# enhanced-dual-joystick.net
KiCad netlist of a schematic drawn in EAGLE
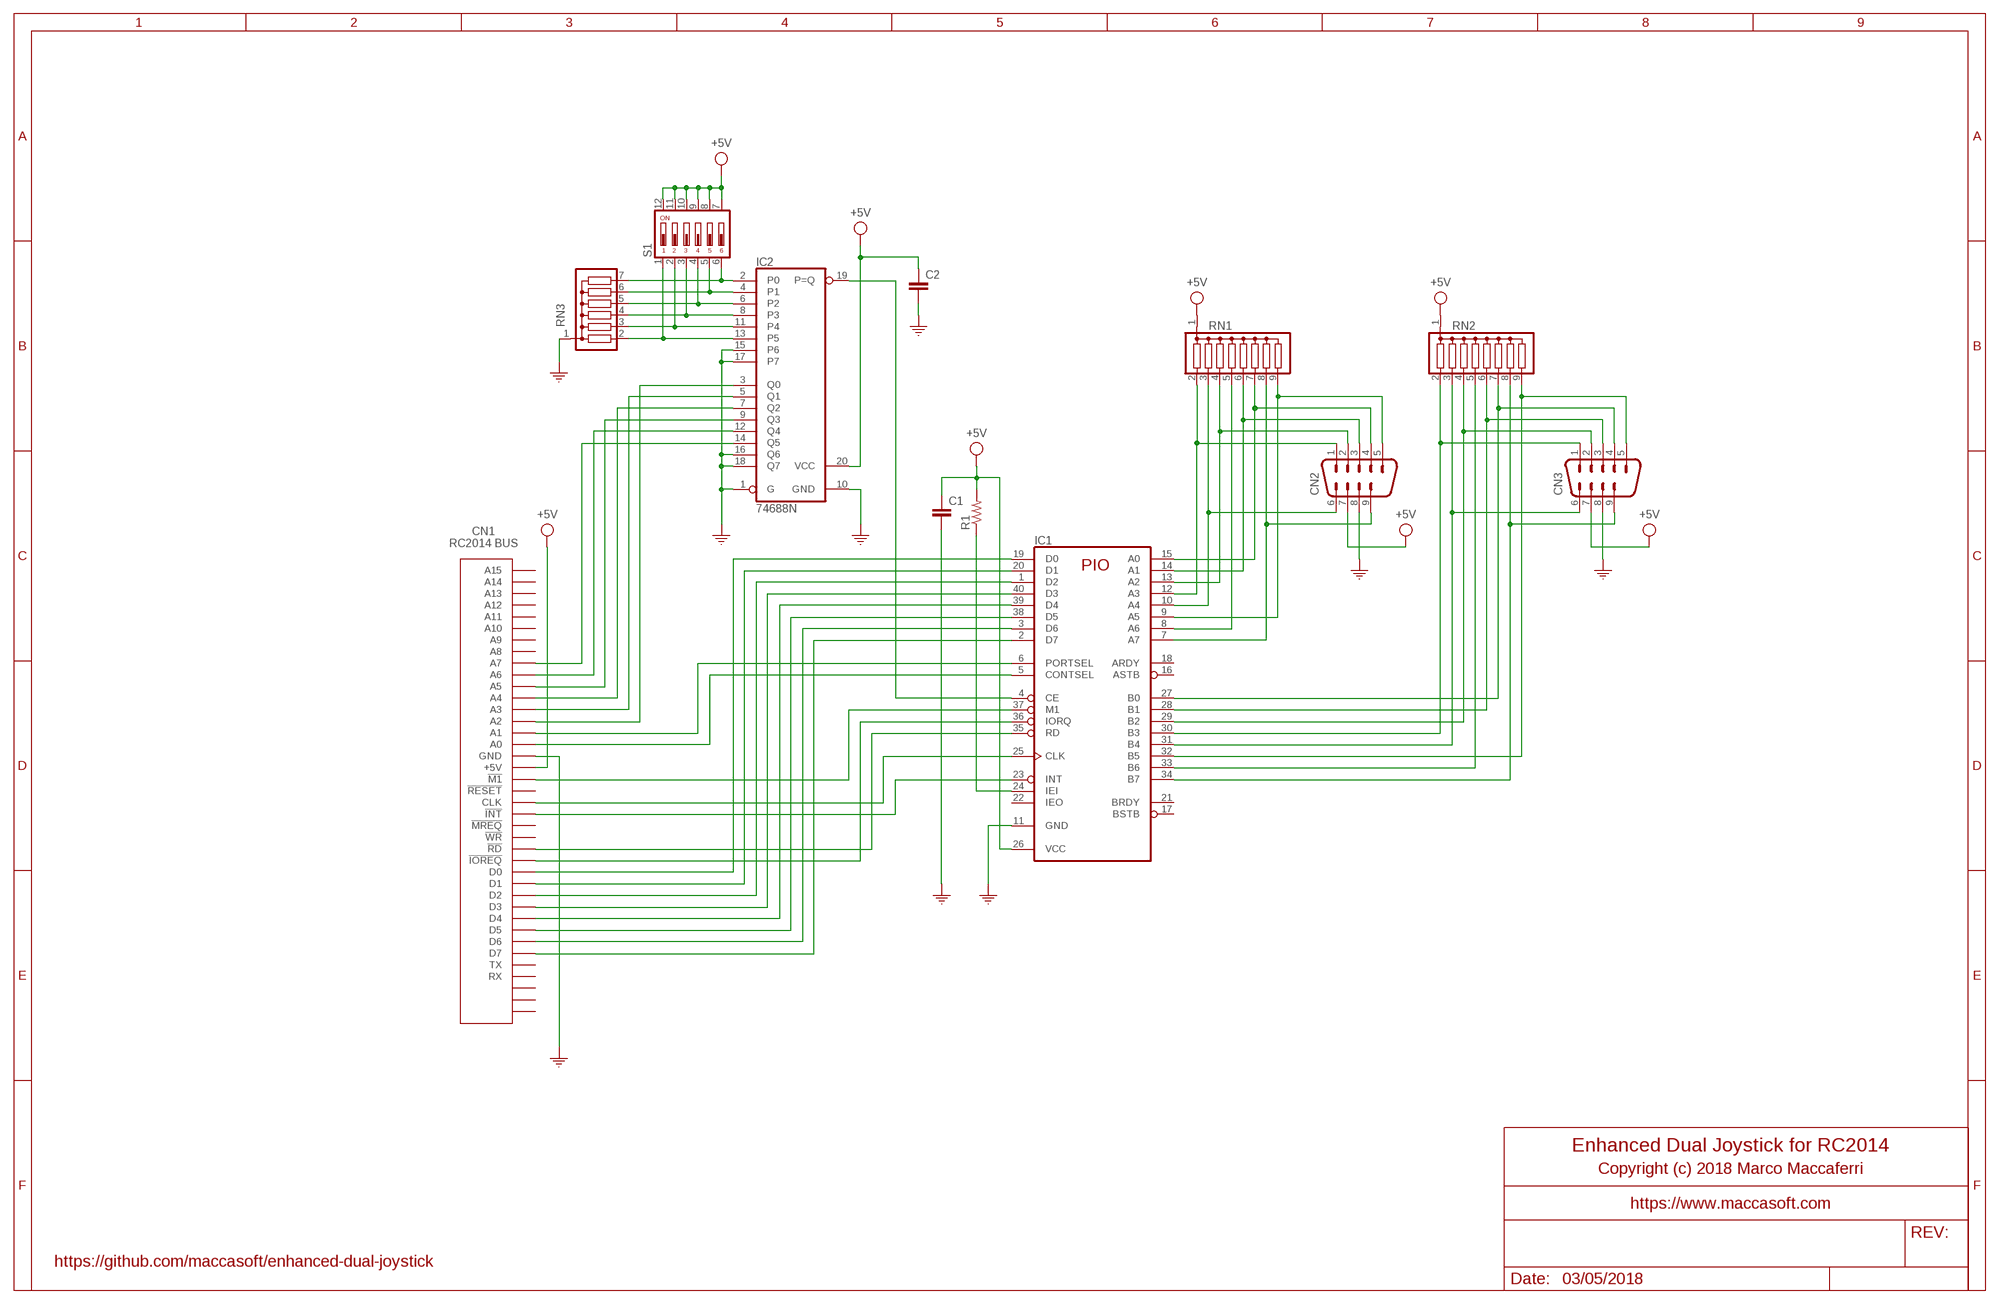
[diagram p0: schematic, sheet 1]

(export (version "E")
  (design (tool "Eeschema 10.0.6"))
  (components
    (comp (ref "C1")
      (value "C-EU050-025X075")
      (footprint "eagle-import:C050-025X075")
      (libsource (lib "eagle-import") (part "C-EU050-025X075"))
    )
    (comp (ref "C2")
      (value "C-EU050-025X075")
      (footprint "eagle-import:C050-025X075")
      (libsource (lib "eagle-import") (part "C-EU050-025X075"))
    )
    (comp (ref "CN1")
      (value "RC2014BUS")
      (footprint "eagle-import:RC2014BUS")
      (fields (field (name "MPN") "PRPC040SBAN-M71RC"))
      (libsource (lib "eagle-import") (part "RC2014BUS"))
    )
    (comp (ref "CN2")
      (value "M09H")
      (footprint "eagle-import:M09H")
      (libsource (lib "eagle-import") (part "M09H"))
    )
    (comp (ref "CN3")
      (value "M09H")
      (footprint "eagle-import:M09H")
      (libsource (lib "eagle-import") (part "M09H"))
    )
    (comp (ref "IC1")
      (value "Z80PIO")
      (footprint "eagle-import:DIL40")
      (libsource (lib "eagle-import") (part "Z80PIO"))
    )
    (comp (ref "IC2")
      (value "74688N")
      (footprint "eagle-import:DIL20")
      (libsource (lib "eagle-import") (part "74688N"))
    )
    (comp (ref "R1")
      (value "R-US_0207/10")
      (footprint "eagle-import:0207_10")
      (libsource (lib "eagle-import") (part "R-US_0207/10"))
    )
    (comp (ref "RN1")
      (value "G08R")
      (footprint "eagle-import:SIL9")
      (libsource (lib "eagle-import") (part "G08R"))
    )
    (comp (ref "RN2")
      (value "G08R")
      (footprint "eagle-import:SIL9")
      (libsource (lib "eagle-import") (part "G08R"))
    )
    (comp (ref "RN3")
      (value "G06R")
      (footprint "eagle-import:SIL7")
      (libsource (lib "eagle-import") (part "G06R"))
    )
    (comp (ref "S1")
      (value "DIP06YL")
      (footprint "eagle-import:DIP06YL")
      (libsource (lib "eagle-import") (part "DIP06YL"))
    )
  )
  (nets
    (net (code "1") (name "+5V") (class "Default")
      (node (ref "C1") (pin "1") (pinfunction "1_1") (pintype "passive"))
      (node (ref "C2") (pin "1") (pinfunction "1_1") (pintype "passive"))
      (node (ref "CN1") (pin "+5V") (pinfunction "+5V_+5V") (pintype "bidirectional"))
      (node (ref "CN2") (pin "7") (pinfunction "7_7") (pintype "passive"))
      (node (ref "CN3") (pin "7") (pinfunction "7_7") (pintype "passive"))
      (node (ref "IC1") (pin "26") (pinfunction "VCC_26") (pintype "power_in"))
      (node (ref "IC2") (pin "20") (pinfunction "VCC_20") (pintype "power_in"))
      (node (ref "R1") (pin "2") (pinfunction "2_2") (pintype "passive"))
      (node (ref "RN1") (pin "1") (pinfunction "1_1") (pintype "passive"))
      (node (ref "RN2") (pin "1") (pinfunction "1_1") (pintype "passive"))
      (node (ref "S1") (pin "10") (pinfunction "10_10") (pintype "passive"))
      (node (ref "S1") (pin "11") (pinfunction "11_11") (pintype "passive"))
      (node (ref "S1") (pin "12") (pinfunction "12_12") (pintype "passive"))
      (node (ref "S1") (pin "7") (pinfunction "7_7") (pintype "passive"))
      (node (ref "S1") (pin "8") (pinfunction "8_8") (pintype "passive"))
      (node (ref "S1") (pin "9") (pinfunction "9_9") (pintype "passive"))
    )
    (net (code "2") (name "GND") (class "Default")
      (node (ref "C1") (pin "2") (pinfunction "2_2") (pintype "passive"))
      (node (ref "C2") (pin "2") (pinfunction "2_2") (pintype "passive"))
      (node (ref "CN1") (pin "GND") (pinfunction "GND_GND") (pintype "bidirectional"))
      (node (ref "CN2") (pin "8") (pinfunction "8_8") (pintype "passive"))
      (node (ref "CN3") (pin "8") (pinfunction "8_8") (pintype "passive"))
      (node (ref "IC1") (pin "11") (pinfunction "GND_11") (pintype "power_in"))
      (node (ref "IC2") (pin "1") (pinfunction "G_1") (pintype "input"))
      (node (ref "IC2") (pin "10") (pinfunction "GND_10") (pintype "power_in"))
      (node (ref "IC2") (pin "15") (pinfunction "P6_15") (pintype "input"))
      (node (ref "IC2") (pin "16") (pinfunction "Q6_16") (pintype "input"))
      (node (ref "IC2") (pin "17") (pinfunction "P7_17") (pintype "input"))
      (node (ref "IC2") (pin "18") (pinfunction "Q7_18") (pintype "input"))
      (node (ref "RN3") (pin "1") (pinfunction "1_1") (pintype "passive"))
    )
    (net (code "3") (name "Net-(CN1-~{INT})") (class "Default")
      (node (ref "CN1") (pin "!INT!") (pinfunction "~{INT}_!INT!") (pintype "bidirectional"))
      (node (ref "IC1") (pin "23") (pinfunction "INT_23") (pintype "output"))
    )
    (net (code "4") (name "Net-(CN1-~{IOREQ})") (class "Default")
      (node (ref "CN1") (pin "!IOREQ!") (pinfunction "~{IOREQ}_!IOREQ!") (pintype "bidirectional"))
      (node (ref "IC1") (pin "36") (pinfunction "IORQ_36") (pintype "input"))
    )
    (net (code "5") (name "Net-(CN1-~{M1})") (class "Default")
      (node (ref "CN1") (pin "!M1!") (pinfunction "~{M1}_!M1!") (pintype "bidirectional"))
      (node (ref "IC1") (pin "37") (pinfunction "M1_37") (pintype "input"))
    )
    (net (code "6") (name "Net-(CN1-~{RD})") (class "Default")
      (node (ref "CN1") (pin "!RD!") (pinfunction "~{RD}_!RD!") (pintype "bidirectional"))
      (node (ref "IC1") (pin "35") (pinfunction "RD_35") (pintype "input"))
    )
    (net (code "7") (name "Net-(IC1-A0)") (class "Default")
      (node (ref "CN2") (pin "4") (pinfunction "4_4") (pintype "passive"))
      (node (ref "IC1") (pin "15") (pinfunction "A0_15") (pintype "bidirectional"))
      (node (ref "RN1") (pin "7") (pinfunction "7_7") (pintype "passive"))
    )
    (net (code "8") (name "Net-(IC1-A1)") (class "Default")
      (node (ref "CN2") (pin "3") (pinfunction "3_3") (pintype "passive"))
      (node (ref "IC1") (pin "14") (pinfunction "A1_14") (pintype "bidirectional"))
      (node (ref "RN1") (pin "6") (pinfunction "6_6") (pintype "passive"))
    )
    (net (code "9") (name "Net-(IC1-A2)") (class "Default")
      (node (ref "CN2") (pin "2") (pinfunction "2_2") (pintype "passive"))
      (node (ref "IC1") (pin "13") (pinfunction "A2_13") (pintype "bidirectional"))
      (node (ref "RN1") (pin "4") (pinfunction "4_4") (pintype "passive"))
    )
    (net (code "10") (name "Net-(IC1-A3)") (class "Default")
      (node (ref "CN2") (pin "1") (pinfunction "1_1") (pintype "passive"))
      (node (ref "IC1") (pin "12") (pinfunction "A3_12") (pintype "bidirectional"))
      (node (ref "RN1") (pin "2") (pinfunction "2_2") (pintype "passive"))
    )
    (net (code "11") (name "Net-(IC1-A4)") (class "Default")
      (node (ref "CN2") (pin "6") (pinfunction "6_6") (pintype "passive"))
      (node (ref "IC1") (pin "10") (pinfunction "A4_10") (pintype "bidirectional"))
      (node (ref "RN1") (pin "3") (pinfunction "3_3") (pintype "passive"))
    )
    (net (code "12") (name "Net-(IC1-A5)") (class "Default")
      (node (ref "CN2") (pin "5") (pinfunction "5_5") (pintype "passive"))
      (node (ref "IC1") (pin "9") (pinfunction "A5_9") (pintype "bidirectional"))
      (node (ref "RN1") (pin "9") (pinfunction "9_9") (pintype "passive"))
    )
    (net (code "13") (name "Net-(IC1-A6)") (class "Default")
      (node (ref "IC1") (pin "8") (pinfunction "A6_8") (pintype "bidirectional"))
      (node (ref "RN1") (pin "5") (pinfunction "5_5") (pintype "passive"))
    )
    (net (code "14") (name "Net-(IC1-A7)") (class "Default")
      (node (ref "CN2") (pin "9") (pinfunction "9_9") (pintype "passive"))
      (node (ref "IC1") (pin "7") (pinfunction "A7_7") (pintype "bidirectional"))
      (node (ref "RN1") (pin "8") (pinfunction "8_8") (pintype "passive"))
    )
    (net (code "15") (name "Net-(IC1-B0)") (class "Default")
      (node (ref "CN3") (pin "4") (pinfunction "4_4") (pintype "passive"))
      (node (ref "IC1") (pin "27") (pinfunction "B0_27") (pintype "bidirectional"))
      (node (ref "RN2") (pin "7") (pinfunction "7_7") (pintype "passive"))
    )
    (net (code "16") (name "Net-(IC1-B1)") (class "Default")
      (node (ref "CN3") (pin "3") (pinfunction "3_3") (pintype "passive"))
      (node (ref "IC1") (pin "28") (pinfunction "B1_28") (pintype "bidirectional"))
      (node (ref "RN2") (pin "6") (pinfunction "6_6") (pintype "passive"))
    )
    (net (code "17") (name "Net-(IC1-B2)") (class "Default")
      (node (ref "CN3") (pin "2") (pinfunction "2_2") (pintype "passive"))
      (node (ref "IC1") (pin "29") (pinfunction "B2_29") (pintype "bidirectional"))
      (node (ref "RN2") (pin "4") (pinfunction "4_4") (pintype "passive"))
    )
    (net (code "18") (name "Net-(IC1-B3)") (class "Default")
      (node (ref "CN3") (pin "1") (pinfunction "1_1") (pintype "passive"))
      (node (ref "IC1") (pin "30") (pinfunction "B3_30") (pintype "bidirectional"))
      (node (ref "RN2") (pin "2") (pinfunction "2_2") (pintype "passive"))
    )
    (net (code "19") (name "Net-(IC1-B4)") (class "Default")
      (node (ref "CN3") (pin "6") (pinfunction "6_6") (pintype "passive"))
      (node (ref "IC1") (pin "31") (pinfunction "B4_31") (pintype "bidirectional"))
      (node (ref "RN2") (pin "3") (pinfunction "3_3") (pintype "passive"))
    )
    (net (code "20") (name "Net-(IC1-B5)") (class "Default")
      (node (ref "CN3") (pin "5") (pinfunction "5_5") (pintype "passive"))
      (node (ref "IC1") (pin "32") (pinfunction "B5_32") (pintype "bidirectional"))
      (node (ref "RN2") (pin "9") (pinfunction "9_9") (pintype "passive"))
    )
    (net (code "21") (name "Net-(IC1-B6)") (class "Default")
      (node (ref "IC1") (pin "33") (pinfunction "B6_33") (pintype "bidirectional"))
      (node (ref "RN2") (pin "5") (pinfunction "5_5") (pintype "passive"))
    )
    (net (code "22") (name "Net-(IC1-B7)") (class "Default")
      (node (ref "CN3") (pin "9") (pinfunction "9_9") (pintype "passive"))
      (node (ref "IC1") (pin "34") (pinfunction "B7_34") (pintype "bidirectional"))
      (node (ref "RN2") (pin "8") (pinfunction "8_8") (pintype "passive"))
    )
    (net (code "23") (name "Net-(IC1-CE)") (class "Default")
      (node (ref "IC1") (pin "4") (pinfunction "CE_4") (pintype "input"))
      (node (ref "IC2") (pin "19") (pinfunction "P=Q_19") (pintype "output"))
    )
    (net (code "24") (name "Net-(IC1-CLK)") (class "Default")
      (node (ref "CN1") (pin "CLK") (pinfunction "CLK_CLK") (pintype "bidirectional"))
      (node (ref "IC1") (pin "25") (pinfunction "CLK_25") (pintype "input"))
    )
    (net (code "25") (name "Net-(IC1-CONTSEL)") (class "Default")
      (node (ref "CN1") (pin "A0") (pinfunction "A0_A0") (pintype "bidirectional"))
      (node (ref "IC1") (pin "5") (pinfunction "CONTSEL_5") (pintype "input"))
    )
    (net (code "26") (name "Net-(IC1-D0)") (class "Default")
      (node (ref "CN1") (pin "D0") (pinfunction "D0_D0") (pintype "bidirectional"))
      (node (ref "IC1") (pin "19") (pinfunction "D0_19") (pintype "bidirectional"))
    )
    (net (code "27") (name "Net-(IC1-D1)") (class "Default")
      (node (ref "CN1") (pin "D1") (pinfunction "D1_D1") (pintype "bidirectional"))
      (node (ref "IC1") (pin "20") (pinfunction "D1_20") (pintype "bidirectional"))
    )
    (net (code "28") (name "Net-(IC1-D2)") (class "Default")
      (node (ref "CN1") (pin "D2") (pinfunction "D2_D2") (pintype "bidirectional"))
      (node (ref "IC1") (pin "1") (pinfunction "D2_1") (pintype "bidirectional"))
    )
    (net (code "29") (name "Net-(IC1-D3)") (class "Default")
      (node (ref "CN1") (pin "D3") (pinfunction "D3_D3") (pintype "bidirectional"))
      (node (ref "IC1") (pin "40") (pinfunction "D3_40") (pintype "bidirectional"))
    )
    (net (code "30") (name "Net-(IC1-D4)") (class "Default")
      (node (ref "CN1") (pin "D4") (pinfunction "D4_D4") (pintype "bidirectional"))
      (node (ref "IC1") (pin "39") (pinfunction "D4_39") (pintype "bidirectional"))
    )
    (net (code "31") (name "Net-(IC1-D5)") (class "Default")
      (node (ref "CN1") (pin "D5") (pinfunction "D5_D5") (pintype "bidirectional"))
      (node (ref "IC1") (pin "38") (pinfunction "D5_38") (pintype "bidirectional"))
    )
    (net (code "32") (name "Net-(IC1-D6)") (class "Default")
      (node (ref "CN1") (pin "D6") (pinfunction "D6_D6") (pintype "bidirectional"))
      (node (ref "IC1") (pin "3") (pinfunction "D6_3") (pintype "bidirectional"))
    )
    (net (code "33") (name "Net-(IC1-D7)") (class "Default")
      (node (ref "CN1") (pin "D7") (pinfunction "D7_D7") (pintype "bidirectional"))
      (node (ref "IC1") (pin "2") (pinfunction "D7_2") (pintype "bidirectional"))
    )
    (net (code "34") (name "Net-(IC1-IEI)") (class "Default")
      (node (ref "IC1") (pin "24") (pinfunction "IEI_24") (pintype "input"))
      (node (ref "R1") (pin "1") (pinfunction "1_1") (pintype "passive"))
    )
    (net (code "35") (name "Net-(IC1-PORTSEL)") (class "Default")
      (node (ref "CN1") (pin "A1") (pinfunction "A1_A1") (pintype "bidirectional"))
      (node (ref "IC1") (pin "6") (pinfunction "PORTSEL_6") (pintype "input"))
    )
    (net (code "36") (name "Net-(IC2-P0)") (class "Default")
      (node (ref "IC2") (pin "2") (pinfunction "P0_2") (pintype "input"))
      (node (ref "RN3") (pin "7") (pinfunction "7_7") (pintype "passive"))
      (node (ref "S1") (pin "6") (pinfunction "6_6") (pintype "passive"))
    )
    (net (code "37") (name "Net-(IC2-P1)") (class "Default")
      (node (ref "IC2") (pin "4") (pinfunction "P1_4") (pintype "input"))
      (node (ref "RN3") (pin "6") (pinfunction "6_6") (pintype "passive"))
      (node (ref "S1") (pin "5") (pinfunction "5_5") (pintype "passive"))
    )
    (net (code "38") (name "Net-(IC2-P2)") (class "Default")
      (node (ref "IC2") (pin "6") (pinfunction "P2_6") (pintype "input"))
      (node (ref "RN3") (pin "5") (pinfunction "5_5") (pintype "passive"))
      (node (ref "S1") (pin "4") (pinfunction "4_4") (pintype "passive"))
    )
    (net (code "39") (name "Net-(IC2-P3)") (class "Default")
      (node (ref "IC2") (pin "8") (pinfunction "P3_8") (pintype "input"))
      (node (ref "RN3") (pin "4") (pinfunction "4_4") (pintype "passive"))
      (node (ref "S1") (pin "3") (pinfunction "3_3") (pintype "passive"))
    )
    (net (code "40") (name "Net-(IC2-P4)") (class "Default")
      (node (ref "IC2") (pin "11") (pinfunction "P4_11") (pintype "input"))
      (node (ref "RN3") (pin "3") (pinfunction "3_3") (pintype "passive"))
      (node (ref "S1") (pin "2") (pinfunction "2_2") (pintype "passive"))
    )
    (net (code "41") (name "Net-(IC2-P5)") (class "Default")
      (node (ref "IC2") (pin "13") (pinfunction "P5_13") (pintype "input"))
      (node (ref "RN3") (pin "2") (pinfunction "2_2") (pintype "passive"))
      (node (ref "S1") (pin "1") (pinfunction "1_1") (pintype "passive"))
    )
    (net (code "42") (name "Net-(IC2-Q0)") (class "Default")
      (node (ref "CN1") (pin "A2") (pinfunction "A2_A2") (pintype "bidirectional"))
      (node (ref "IC2") (pin "3") (pinfunction "Q0_3") (pintype "input"))
    )
    (net (code "43") (name "Net-(IC2-Q1)") (class "Default")
      (node (ref "CN1") (pin "A3") (pinfunction "A3_A3") (pintype "bidirectional"))
      (node (ref "IC2") (pin "5") (pinfunction "Q1_5") (pintype "input"))
    )
    (net (code "44") (name "Net-(IC2-Q2)") (class "Default")
      (node (ref "CN1") (pin "A4") (pinfunction "A4_A4") (pintype "bidirectional"))
      (node (ref "IC2") (pin "7") (pinfunction "Q2_7") (pintype "input"))
    )
    (net (code "45") (name "Net-(IC2-Q3)") (class "Default")
      (node (ref "CN1") (pin "A5") (pinfunction "A5_A5") (pintype "bidirectional"))
      (node (ref "IC2") (pin "9") (pinfunction "Q3_9") (pintype "input"))
    )
    (net (code "46") (name "Net-(IC2-Q4)") (class "Default")
      (node (ref "CN1") (pin "A6") (pinfunction "A6_A6") (pintype "bidirectional"))
      (node (ref "IC2") (pin "12") (pinfunction "Q4_12") (pintype "input"))
    )
    (net (code "47") (name "Net-(IC2-Q5)") (class "Default")
      (node (ref "CN1") (pin "A7") (pinfunction "A7_A7") (pintype "bidirectional"))
      (node (ref "IC2") (pin "14") (pinfunction "Q5_14") (pintype "input"))
    )
    (net (code "48") (name "unconnected-(CN1-PadA8)") (class "Default")
      (node (ref "CN1") (pin "A8") (pinfunction "A8_A8") (pintype "bidirectional"))
    )
    (net (code "49") (name "unconnected-(CN1-PadA9)") (class "Default")
      (node (ref "CN1") (pin "A9") (pinfunction "A9_A9") (pintype "bidirectional"))
    )
    (net (code "50") (name "unconnected-(CN1-PadA10)") (class "Default")
      (node (ref "CN1") (pin "A10") (pinfunction "A10_A10") (pintype "bidirectional"))
    )
    (net (code "51") (name "unconnected-(CN1-PadA11)") (class "Default")
      (node (ref "CN1") (pin "A11") (pinfunction "A11_A11") (pintype "bidirectional"))
    )
    (net (code "52") (name "unconnected-(CN1-PadA12)") (class "Default")
      (node (ref "CN1") (pin "A12") (pinfunction "A12_A12") (pintype "bidirectional"))
    )
    (net (code "53") (name "unconnected-(CN1-PadA13)") (class "Default")
      (node (ref "CN1") (pin "A13") (pinfunction "A13_A13") (pintype "bidirectional"))
    )
    (net (code "54") (name "unconnected-(CN1-PadA14)") (class "Default")
      (node (ref "CN1") (pin "A14") (pinfunction "A14_A14") (pintype "bidirectional"))
    )
    (net (code "55") (name "unconnected-(CN1-PadA15)") (class "Default")
      (node (ref "CN1") (pin "A15") (pinfunction "A15_A15") (pintype "bidirectional"))
    )
    (net (code "56") (name "unconnected-(CN1-PadRX)") (class "Default")
      (node (ref "CN1") (pin "RX") (pinfunction "RX_RX") (pintype "bidirectional"))
    )
    (net (code "57") (name "unconnected-(CN1-PadSPARE1)") (class "Default")
      (node (ref "CN1") (pin "SPARE1") (pinfunction "SPARE1_SPARE1") (pintype "bidirectional"))
    )
    (net (code "58") (name "unconnected-(CN1-PadSPARE2)") (class "Default")
      (node (ref "CN1") (pin "SPARE2") (pinfunction "SPARE2_SPARE2") (pintype "bidirectional"))
    )
    (net (code "59") (name "unconnected-(CN1-PadSPARE3)") (class "Default")
      (node (ref "CN1") (pin "SPARE3") (pinfunction "SPARE3_SPARE3") (pintype "bidirectional"))
    )
    (net (code "60") (name "unconnected-(CN1-PadTX)") (class "Default")
      (node (ref "CN1") (pin "TX") (pinfunction "TX_TX") (pintype "bidirectional"))
    )
    (net (code "61") (name "unconnected-(CN1-~{MREQ}-Pad!MREQ!)") (class "Default")
      (node (ref "CN1") (pin "!MREQ!") (pinfunction "~{MREQ}_!MREQ!") (pintype "bidirectional"))
    )
    (net (code "62") (name "unconnected-(CN1-~{RESET}-Pad!RESET!)") (class "Default")
      (node (ref "CN1") (pin "!RESET!") (pinfunction "~{RESET}_!RESET!") (pintype "bidirectional"))
    )
    (net (code "63") (name "unconnected-(CN1-~{WR}-Pad!WR!)") (class "Default")
      (node (ref "CN1") (pin "!WR!") (pinfunction "~{WR}_!WR!") (pintype "bidirectional"))
    )
    (net (code "64") (name "unconnected-(IC1-ARDY-Pad18)") (class "Default")
      (node (ref "IC1") (pin "18") (pinfunction "ARDY_18") (pintype "output"))
    )
    (net (code "65") (name "unconnected-(IC1-ASTB-Pad16)") (class "Default")
      (node (ref "IC1") (pin "16") (pinfunction "ASTB_16") (pintype "input"))
    )
    (net (code "66") (name "unconnected-(IC1-BRDY-Pad21)") (class "Default")
      (node (ref "IC1") (pin "21") (pinfunction "BRDY_21") (pintype "output"))
    )
    (net (code "67") (name "unconnected-(IC1-BSTB-Pad17)") (class "Default")
      (node (ref "IC1") (pin "17") (pinfunction "BSTB_17") (pintype "input"))
    )
    (net (code "68") (name "unconnected-(IC1-IEO-Pad22)") (class "Default")
      (node (ref "IC1") (pin "22") (pinfunction "IEO_22") (pintype "output"))
    )
  )
)
